# levelshift.net
KiCad netlist of a schematic drawn in EAGLE
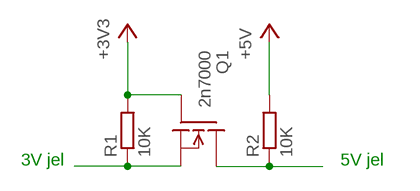
[diagram p0: schematic, sheet 1]

(export (version "E")
  (design (tool "Eeschema 10.0.6"))
  (components
    (comp (ref "Q1")
      (value "2n7000")
      (footprint "eagle-import:TO202")
      (libsource (lib "eagle-import") (part "BSS97"))
    )
    (comp (ref "R1")
      (value "10K")
      (footprint "eagle-import:0309_12")
      (libsource (lib "eagle-import") (part "R-EU_0309/12"))
    )
    (comp (ref "R2")
      (value "10K")
      (footprint "eagle-import:0309_12")
      (libsource (lib "eagle-import") (part "R-EU_0309/12"))
    )
  )
  (nets
    (net (code "1") (name "+3V3") (class "Default")
      (node (ref "Q1") (pin "3") (pinfunction "G_3") (pintype "passive"))
      (node (ref "R1") (pin "2") (pinfunction "2_2") (pintype "passive"))
    )
    (net (code "2") (name "+5V") (class "Default")
      (node (ref "R2") (pin "2") (pinfunction "2_2") (pintype "passive"))
    )
    (net (code "3") (name "Net-(Q1-D)") (class "Default")
      (node (ref "Q1") (pin "2") (pinfunction "D_2") (pintype "passive"))
      (node (ref "R2") (pin "1") (pinfunction "1_1") (pintype "passive"))
    )
    (net (code "4") (name "Net-(Q1-S)") (class "Default")
      (node (ref "Q1") (pin "1") (pinfunction "S_1") (pintype "passive"))
      (node (ref "R1") (pin "1") (pinfunction "1_1") (pintype "passive"))
    )
  )
)
